# Nusbio_FT232H.net
KiCad netlist of a schematic drawn in EAGLE
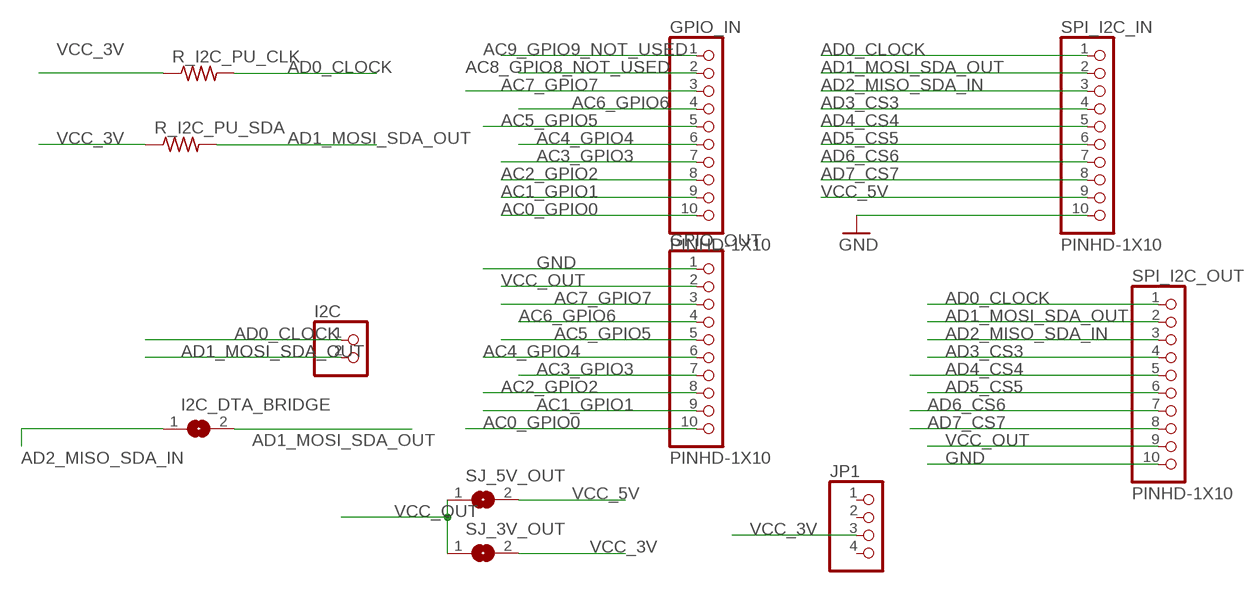
[diagram p0: schematic, sheet 1]

(export (version "E")
  (design (tool "Eeschema 10.0.6"))
  (components
    (comp (ref "GPIO_IN")
      (value "PINHD-1X10")
      (footprint "eagle-import:1X10-BIG")
      (libsource (lib "eagle-import") (part "PINHD-1X10"))
    )
    (comp (ref "GPIO_OUT")
      (value "PINHD-1X10")
      (footprint "eagle-import:1X10-BIG")
      (libsource (lib "eagle-import") (part "PINHD-1X10"))
    )
    (comp (ref "I2C")
      (value "PINHD-1X2")
      (footprint "eagle-import:1X02")
      (libsource (lib "eagle-import") (part "PINHD-1X2"))
    )
    (comp (ref "I2C_DTA_BRIDGE")
      (value "SOLDERJUMPERREFLOW")
      (footprint "eagle-import:SOLDERJUMPER_REFLOW")
      (libsource (lib "eagle-import") (part "SOLDERJUMPERREFLOW"))
    )
    (comp (ref "JP1")
      (value "PINHD-1X4")
      (footprint "eagle-import:1X04")
      (libsource (lib "eagle-import") (part "PINHD-1X4"))
    )
    (comp (ref "R_I2C_PU_CLK")
      (value "R-US_R1206")
      (footprint "eagle-import:R1206")
      (libsource (lib "eagle-import") (part "R-US_R1206"))
    )
    (comp (ref "R_I2C_PU_SDA")
      (value "R-US_R1206")
      (footprint "eagle-import:R1206")
      (libsource (lib "eagle-import") (part "R-US_R1206"))
    )
    (comp (ref "SJ_3V_OUT")
      (value "SOLDERJUMPERREFLOW")
      (footprint "eagle-import:SOLDERJUMPER_REFLOW")
      (libsource (lib "eagle-import") (part "SOLDERJUMPERREFLOW"))
    )
    (comp (ref "SJ_5V_OUT")
      (value "SOLDERJUMPERREFLOW")
      (footprint "eagle-import:SOLDERJUMPER_REFLOW")
      (libsource (lib "eagle-import") (part "SOLDERJUMPERREFLOW"))
    )
    (comp (ref "SPI_I2C_IN")
      (value "PINHD-1X10")
      (footprint "eagle-import:1X10-BIG")
      (libsource (lib "eagle-import") (part "PINHD-1X10"))
    )
    (comp (ref "SPI_I2C_OUT")
      (value "PINHD-1X10")
      (footprint "eagle-import:1X10-BIG")
      (libsource (lib "eagle-import") (part "PINHD-1X10"))
    )
  )
  (nets
    (net (code "1") (name "/AC0_GPIO0") (class "Default")
      (node (ref "GPIO_IN") (pin "10") (pinfunction "10_10") (pintype "passive"))
      (node (ref "GPIO_OUT") (pin "10") (pinfunction "10_10") (pintype "passive"))
    )
    (net (code "2") (name "/AC1_GPIO1") (class "Default")
      (node (ref "GPIO_IN") (pin "9") (pinfunction "9_9") (pintype "passive"))
      (node (ref "GPIO_OUT") (pin "9") (pinfunction "9_9") (pintype "passive"))
    )
    (net (code "3") (name "/AC2_GPIO2") (class "Default")
      (node (ref "GPIO_IN") (pin "8") (pinfunction "8_8") (pintype "passive"))
      (node (ref "GPIO_OUT") (pin "8") (pinfunction "8_8") (pintype "passive"))
    )
    (net (code "4") (name "/AC3_GPIO3") (class "Default")
      (node (ref "GPIO_IN") (pin "7") (pinfunction "7_7") (pintype "passive"))
      (node (ref "GPIO_OUT") (pin "7") (pinfunction "7_7") (pintype "passive"))
    )
    (net (code "5") (name "/AC4_GPIO4") (class "Default")
      (node (ref "GPIO_IN") (pin "6") (pinfunction "6_6") (pintype "passive"))
      (node (ref "GPIO_OUT") (pin "6") (pinfunction "6_6") (pintype "passive"))
    )
    (net (code "6") (name "/AC5_GPIO5") (class "Default")
      (node (ref "GPIO_IN") (pin "5") (pinfunction "5_5") (pintype "passive"))
      (node (ref "GPIO_OUT") (pin "5") (pinfunction "5_5") (pintype "passive"))
    )
    (net (code "7") (name "/AC6_GPIO6") (class "Default")
      (node (ref "GPIO_IN") (pin "4") (pinfunction "4_4") (pintype "passive"))
      (node (ref "GPIO_OUT") (pin "4") (pinfunction "4_4") (pintype "passive"))
    )
    (net (code "8") (name "/AC7_GPIO7") (class "Default")
      (node (ref "GPIO_IN") (pin "3") (pinfunction "3_3") (pintype "passive"))
      (node (ref "GPIO_OUT") (pin "3") (pinfunction "3_3") (pintype "passive"))
    )
    (net (code "9") (name "/AC8_GPIO8_NOT_USED") (class "Default")
      (node (ref "GPIO_IN") (pin "2") (pinfunction "2_2") (pintype "passive"))
    )
    (net (code "10") (name "/AC9_GPIO9_NOT_USED") (class "Default")
      (node (ref "GPIO_IN") (pin "1") (pinfunction "1_1") (pintype "passive"))
    )
    (net (code "11") (name "/AD0_CLOCK") (class "Default")
      (node (ref "I2C") (pin "1") (pinfunction "1_1") (pintype "passive"))
      (node (ref "R_I2C_PU_CLK") (pin "2") (pinfunction "2_2") (pintype "passive"))
      (node (ref "SPI_I2C_IN") (pin "1") (pinfunction "1_1") (pintype "passive"))
      (node (ref "SPI_I2C_OUT") (pin "1") (pinfunction "1_1") (pintype "passive"))
    )
    (net (code "12") (name "/AD1_MOSI_SDA_OUT") (class "Default")
      (node (ref "I2C") (pin "2") (pinfunction "2_2") (pintype "passive"))
      (node (ref "I2C_DTA_BRIDGE") (pin "2") (pinfunction "2_2") (pintype "passive"))
      (node (ref "R_I2C_PU_SDA") (pin "2") (pinfunction "2_2") (pintype "passive"))
      (node (ref "SPI_I2C_IN") (pin "2") (pinfunction "2_2") (pintype "passive"))
      (node (ref "SPI_I2C_OUT") (pin "2") (pinfunction "2_2") (pintype "passive"))
    )
    (net (code "13") (name "/AD2_MISO_SDA_IN") (class "Default")
      (node (ref "I2C_DTA_BRIDGE") (pin "1") (pinfunction "1_1") (pintype "passive"))
      (node (ref "SPI_I2C_IN") (pin "3") (pinfunction "3_3") (pintype "passive"))
      (node (ref "SPI_I2C_OUT") (pin "3") (pinfunction "3_3") (pintype "passive"))
    )
    (net (code "14") (name "/AD3_CS3") (class "Default")
      (node (ref "SPI_I2C_IN") (pin "4") (pinfunction "4_4") (pintype "passive"))
      (node (ref "SPI_I2C_OUT") (pin "4") (pinfunction "4_4") (pintype "passive"))
    )
    (net (code "15") (name "/AD4_CS4") (class "Default")
      (node (ref "SPI_I2C_IN") (pin "5") (pinfunction "5_5") (pintype "passive"))
      (node (ref "SPI_I2C_OUT") (pin "5") (pinfunction "5_5") (pintype "passive"))
    )
    (net (code "16") (name "/AD5_CS5") (class "Default")
      (node (ref "SPI_I2C_IN") (pin "6") (pinfunction "6_6") (pintype "passive"))
      (node (ref "SPI_I2C_OUT") (pin "6") (pinfunction "6_6") (pintype "passive"))
    )
    (net (code "17") (name "/AD6_CS6") (class "Default")
      (node (ref "SPI_I2C_IN") (pin "7") (pinfunction "7_7") (pintype "passive"))
      (node (ref "SPI_I2C_OUT") (pin "7") (pinfunction "7_7") (pintype "passive"))
    )
    (net (code "18") (name "/AD7_CS7") (class "Default")
      (node (ref "SPI_I2C_IN") (pin "8") (pinfunction "8_8") (pintype "passive"))
      (node (ref "SPI_I2C_OUT") (pin "8") (pinfunction "8_8") (pintype "passive"))
    )
    (net (code "19") (name "/VCC_3V") (class "Default")
      (node (ref "JP1") (pin "3") (pinfunction "3_3") (pintype "passive"))
      (node (ref "R_I2C_PU_CLK") (pin "1") (pinfunction "1_1") (pintype "passive"))
      (node (ref "R_I2C_PU_SDA") (pin "1") (pinfunction "1_1") (pintype "passive"))
      (node (ref "SJ_3V_OUT") (pin "2") (pinfunction "2_2") (pintype "passive"))
    )
    (net (code "20") (name "/VCC_5V") (class "Default")
      (node (ref "SJ_5V_OUT") (pin "2") (pinfunction "2_2") (pintype "passive"))
      (node (ref "SPI_I2C_IN") (pin "9") (pinfunction "9_9") (pintype "passive"))
    )
    (net (code "21") (name "/VCC_OUT") (class "Default")
      (node (ref "GPIO_OUT") (pin "2") (pinfunction "2_2") (pintype "passive"))
      (node (ref "SJ_3V_OUT") (pin "1") (pinfunction "1_1") (pintype "passive"))
      (node (ref "SJ_5V_OUT") (pin "1") (pinfunction "1_1") (pintype "passive"))
      (node (ref "SPI_I2C_OUT") (pin "9") (pinfunction "9_9") (pintype "passive"))
    )
    (net (code "22") (name "GND") (class "Default")
      (node (ref "GPIO_OUT") (pin "1") (pinfunction "1_1") (pintype "passive"))
      (node (ref "SPI_I2C_IN") (pin "10") (pinfunction "10_10") (pintype "passive"))
      (node (ref "SPI_I2C_OUT") (pin "10") (pinfunction "10_10") (pintype "passive"))
    )
    (net (code "23") (name "unconnected-(JP1-Pad1)") (class "Default")
      (node (ref "JP1") (pin "1") (pinfunction "1_1") (pintype "passive"))
    )
    (net (code "24") (name "unconnected-(JP1-Pad2)") (class "Default")
      (node (ref "JP1") (pin "2") (pinfunction "2_2") (pintype "passive"))
    )
    (net (code "25") (name "unconnected-(JP1-Pad4)") (class "Default")
      (node (ref "JP1") (pin "4") (pinfunction "4_4") (pintype "passive"))
    )
  )
)
